# pstage.net
KiCad netlist of a schematic drawn in EAGLE
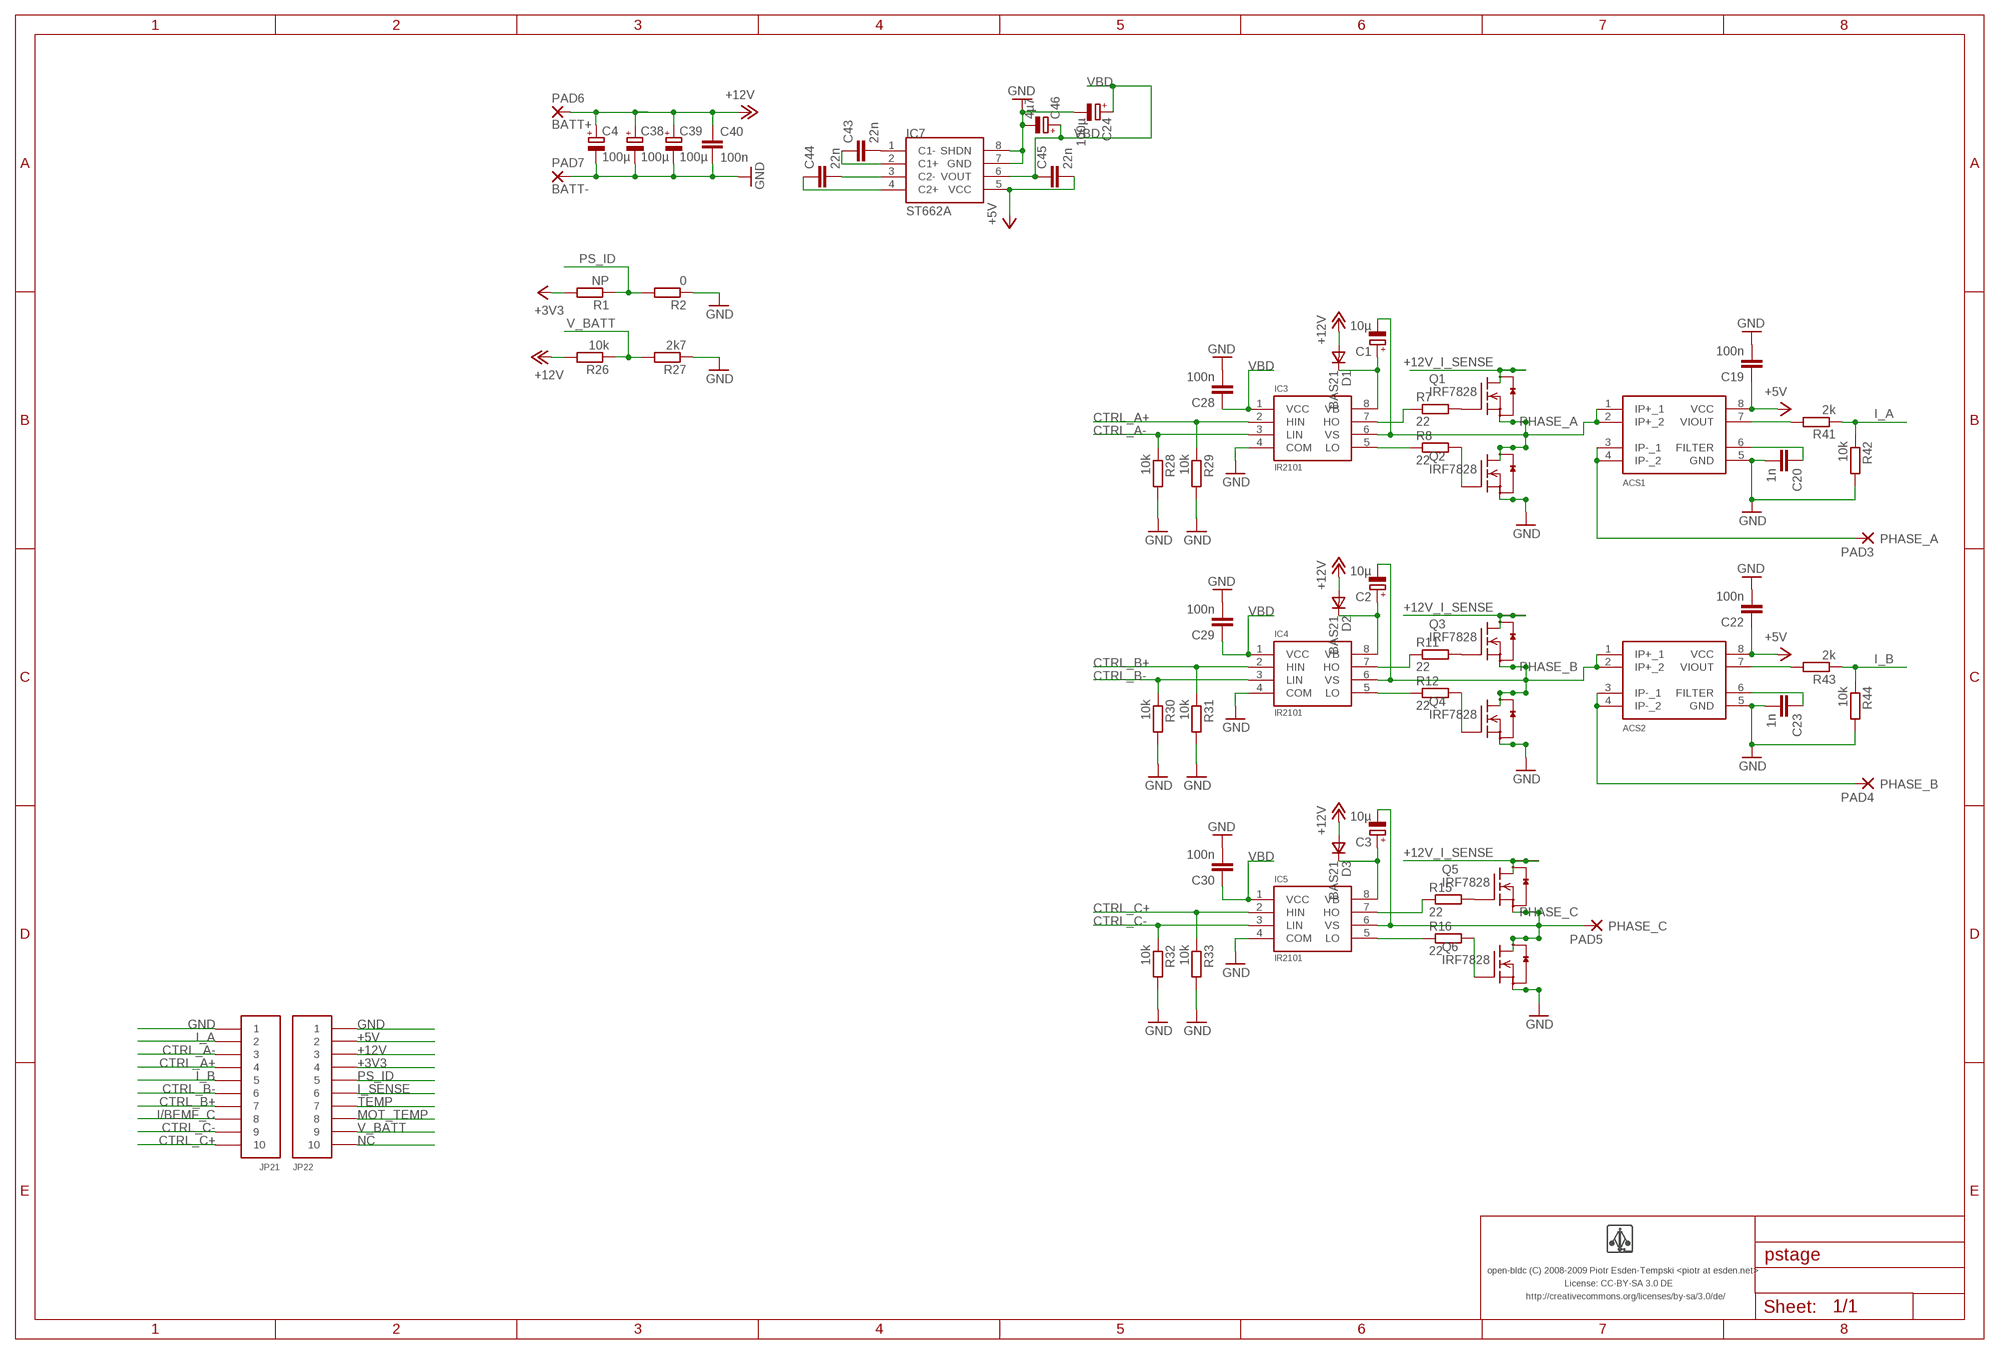
[diagram p0: schematic, sheet 1]

(export (version "E")
  (design (tool "Eeschema 10.0.6"))
  (components
    (comp (ref "ACS1")
      (value "ACS712")
      (footprint "eagle-import:SO8")
      (libsource (lib "eagle-import") (part "ACS712"))
    )
    (comp (ref "ACS2")
      (value "ACS712")
      (footprint "eagle-import:SO8")
      (libsource (lib "eagle-import") (part "ACS712"))
    )
    (comp (ref "C1")
      (value "10µ")
      (footprint "eagle-import:A_3216-18R")
      (libsource (lib "eagle-import") (part "CPOL-EUA/3216-18R"))
    )
    (comp (ref "C2")
      (value "10µ")
      (footprint "eagle-import:A_3216-18R")
      (libsource (lib "eagle-import") (part "CPOL-EUA/3216-18R"))
    )
    (comp (ref "C3")
      (value "10µ")
      (footprint "eagle-import:A_3216-18R")
      (libsource (lib "eagle-import") (part "CPOL-EUA/3216-18R"))
    )
    (comp (ref "C4")
      (value "100µ")
      (footprint "eagle-import:D_7343-31R")
      (libsource (lib "eagle-import") (part "CPOL-EUD/7343-31R"))
    )
    (comp (ref "C19")
      (value "100n")
      (footprint "eagle-import:C0603")
      (libsource (lib "eagle-import") (part "C-EUC0603"))
    )
    (comp (ref "C20")
      (value "1n")
      (footprint "eagle-import:C0603")
      (libsource (lib "eagle-import") (part "C-EUC0603"))
    )
    (comp (ref "C22")
      (value "100n")
      (footprint "eagle-import:C0603")
      (libsource (lib "eagle-import") (part "C-EUC0603"))
    )
    (comp (ref "C23")
      (value "1n")
      (footprint "eagle-import:C0603")
      (libsource (lib "eagle-import") (part "C-EUC0603"))
    )
    (comp (ref "C24")
      (value "100µ")
      (footprint "eagle-import:D_7343-31R")
      (libsource (lib "eagle-import") (part "CPOL-EUD/7343-31R"))
    )
    (comp (ref "C28")
      (value "100n")
      (footprint "eagle-import:C0603")
      (libsource (lib "eagle-import") (part "C-EUC0603"))
    )
    (comp (ref "C29")
      (value "100n")
      (footprint "eagle-import:C0603")
      (libsource (lib "eagle-import") (part "C-EUC0603"))
    )
    (comp (ref "C30")
      (value "100n")
      (footprint "eagle-import:C0603")
      (libsource (lib "eagle-import") (part "C-EUC0603"))
    )
    (comp (ref "C38")
      (value "100µ")
      (footprint "eagle-import:D_7343-31R")
      (libsource (lib "eagle-import") (part "CPOL-EUD/7343-31R"))
    )
    (comp (ref "C39")
      (value "100µ")
      (footprint "eagle-import:D_7343-31R")
      (libsource (lib "eagle-import") (part "CPOL-EUD/7343-31R"))
    )
    (comp (ref "C40")
      (value "100n")
      (footprint "eagle-import:C0603")
      (libsource (lib "eagle-import") (part "C-EUC0603"))
    )
    (comp (ref "C43")
      (value "22n")
      (footprint "eagle-import:C0603")
      (libsource (lib "eagle-import") (part "C-EUC0603"))
    )
    (comp (ref "C44")
      (value "22n")
      (footprint "eagle-import:C0603")
      (libsource (lib "eagle-import") (part "C-EUC0603"))
    )
    (comp (ref "C45")
      (value "22n")
      (footprint "eagle-import:C0603")
      (libsource (lib "eagle-import") (part "C-EUC0603"))
    )
    (comp (ref "C46")
      (value "4µ7")
      (footprint "eagle-import:A_3216-18R")
      (libsource (lib "eagle-import") (part "CPOL-EUA/3216-18R"))
    )
    (comp (ref "D1")
      (value "BAS21")
      (footprint "eagle-import:SOT-23")
      (libsource (lib "eagle-import") (part "VAR2SOT23"))
    )
    (comp (ref "D2")
      (value "BAS21")
      (footprint "eagle-import:SOT-23")
      (libsource (lib "eagle-import") (part "VAR2SOT23"))
    )
    (comp (ref "D3")
      (value "BAS21")
      (footprint "eagle-import:SOT-23")
      (libsource (lib "eagle-import") (part "VAR2SOT23"))
    )
    (comp (ref "IC3")
      (value "IR2101")
      (footprint "eagle-import:SO-8")
      (libsource (lib "eagle-import") (part "IR2101"))
    )
    (comp (ref "IC4")
      (value "IR2101")
      (footprint "eagle-import:SO-8")
      (libsource (lib "eagle-import") (part "IR2101"))
    )
    (comp (ref "IC5")
      (value "IR2101")
      (footprint "eagle-import:SO-8")
      (libsource (lib "eagle-import") (part "IR2101"))
    )
    (comp (ref "IC7")
      (value "ST662A")
      (footprint "eagle-import:SO8")
      (libsource (lib "eagle-import") (part "ST662A"))
    )
    (comp (ref "JP21")
      (value "PIN_HDR_1.27MM_10")
      (footprint "eagle-import:PIN_HDR_1.27MM_10")
      (libsource (lib "eagle-import") (part "PIN_HDR_1.27MM_10_TH"))
    )
    (comp (ref "JP22")
      (value "PIN_HDR_1.27MM_10")
      (footprint "eagle-import:PIN_HDR_1.27MM_10")
      (libsource (lib "eagle-import") (part "PIN_HDR_1.27MM_10_TH"))
    )
    (comp (ref "PAD3")
      (value "PHASE_A")
      (footprint "eagle-import:SMD2,54-5,08")
      (libsource (lib "eagle-import") (part "SMD5"))
    )
    (comp (ref "PAD4")
      (value "PHASE_B")
      (footprint "eagle-import:SMD2,54-5,08")
      (libsource (lib "eagle-import") (part "SMD5"))
    )
    (comp (ref "PAD5")
      (value "PHASE_C")
      (footprint "eagle-import:SMD2,54-5,08")
      (libsource (lib "eagle-import") (part "SMD5"))
    )
    (comp (ref "PAD6")
      (value "BATT+")
      (footprint "eagle-import:SMD2,54-5,08")
      (libsource (lib "eagle-import") (part "SMD5"))
    )
    (comp (ref "PAD7")
      (value "BATT-")
      (footprint "eagle-import:SMD2,54-5,08")
      (libsource (lib "eagle-import") (part "SMD5"))
    )
    (comp (ref "Q1")
      (value "IRF7828")
      (footprint "eagle-import:SO8")
      (libsource (lib "eagle-import") (part "IRF7828"))
    )
    (comp (ref "Q2")
      (value "IRF7828")
      (footprint "eagle-import:SO8")
      (libsource (lib "eagle-import") (part "IRF7828"))
    )
    (comp (ref "Q3")
      (value "IRF7828")
      (footprint "eagle-import:SO8")
      (libsource (lib "eagle-import") (part "IRF7828"))
    )
    (comp (ref "Q4")
      (value "IRF7828")
      (footprint "eagle-import:SO8")
      (libsource (lib "eagle-import") (part "IRF7828"))
    )
    (comp (ref "Q5")
      (value "IRF7828")
      (footprint "eagle-import:SO8")
      (libsource (lib "eagle-import") (part "IRF7828"))
    )
    (comp (ref "Q6")
      (value "IRF7828")
      (footprint "eagle-import:SO8")
      (libsource (lib "eagle-import") (part "IRF7828"))
    )
    (comp (ref "R1")
      (value "NP")
      (footprint "eagle-import:R0603")
      (libsource (lib "eagle-import") (part "R-EU_R0603"))
    )
    (comp (ref "R2")
      (value "0")
      (footprint "eagle-import:R0603")
      (libsource (lib "eagle-import") (part "R-EU_R0603"))
    )
    (comp (ref "R7")
      (value "22")
      (footprint "eagle-import:R0603")
      (libsource (lib "eagle-import") (part "R-EU_R0603"))
    )
    (comp (ref "R8")
      (value "22")
      (footprint "eagle-import:R0603")
      (libsource (lib "eagle-import") (part "R-EU_R0603"))
    )
    (comp (ref "R11")
      (value "22")
      (footprint "eagle-import:R0603")
      (libsource (lib "eagle-import") (part "R-EU_R0603"))
    )
    (comp (ref "R12")
      (value "22")
      (footprint "eagle-import:R0603")
      (libsource (lib "eagle-import") (part "R-EU_R0603"))
    )
    (comp (ref "R15")
      (value "22")
      (footprint "eagle-import:R0603")
      (libsource (lib "eagle-import") (part "R-EU_R0603"))
    )
    (comp (ref "R16")
      (value "22")
      (footprint "eagle-import:R0603")
      (libsource (lib "eagle-import") (part "R-EU_R0603"))
    )
    (comp (ref "R26")
      (value "10k")
      (footprint "eagle-import:R0603")
      (libsource (lib "eagle-import") (part "R-EU_R0603"))
    )
    (comp (ref "R27")
      (value "2k7")
      (footprint "eagle-import:R0603")
      (libsource (lib "eagle-import") (part "R-EU_R0603"))
    )
    (comp (ref "R28")
      (value "10k")
      (footprint "eagle-import:R0603")
      (libsource (lib "eagle-import") (part "R-EU_R0603"))
    )
    (comp (ref "R29")
      (value "10k")
      (footprint "eagle-import:R0603")
      (libsource (lib "eagle-import") (part "R-EU_R0603"))
    )
    (comp (ref "R30")
      (value "10k")
      (footprint "eagle-import:R0603")
      (libsource (lib "eagle-import") (part "R-EU_R0603"))
    )
    (comp (ref "R31")
      (value "10k")
      (footprint "eagle-import:R0603")
      (libsource (lib "eagle-import") (part "R-EU_R0603"))
    )
    (comp (ref "R32")
      (value "10k")
      (footprint "eagle-import:R0603")
      (libsource (lib "eagle-import") (part "R-EU_R0603"))
    )
    (comp (ref "R33")
      (value "10k")
      (footprint "eagle-import:R0603")
      (libsource (lib "eagle-import") (part "R-EU_R0603"))
    )
    (comp (ref "R41")
      (value "2k")
      (footprint "eagle-import:R0603")
      (libsource (lib "eagle-import") (part "R-EU_R0603"))
    )
    (comp (ref "R42")
      (value "10k")
      (footprint "eagle-import:R0603")
      (libsource (lib "eagle-import") (part "R-EU_R0603"))
    )
    (comp (ref "R43")
      (value "2k")
      (footprint "eagle-import:R0603")
      (libsource (lib "eagle-import") (part "R-EU_R0603"))
    )
    (comp (ref "R44")
      (value "10k")
      (footprint "eagle-import:R0603")
      (libsource (lib "eagle-import") (part "R-EU_R0603"))
    )
    (comp (ref "U$1")
      (value "LOGO")
      (footprint "eagle-import:LOGO")
      (libsource (lib "eagle-import") (part "LOGO"))
    )
  )
  (nets
    (net (code "1") (name "+3V3") (class "Default")
      (node (ref "JP22") (pin "P$4") (pinfunction "4_P$4") (pintype "bidirectional"))
      (node (ref "R1") (pin "2") (pinfunction "2_2") (pintype "passive"))
    )
    (net (code "2") (name "+5V") (class "Default")
      (node (ref "ACS1") (pin "8") (pinfunction "VCC_8") (pintype "bidirectional"))
      (node (ref "ACS2") (pin "8") (pinfunction "VCC_8") (pintype "bidirectional"))
      (node (ref "C19") (pin "1") (pinfunction "1_1") (pintype "passive"))
      (node (ref "C22") (pin "1") (pinfunction "1_1") (pintype "passive"))
      (node (ref "C45") (pin "2") (pinfunction "2_2") (pintype "passive"))
      (node (ref "IC7") (pin "5") (pinfunction "VCC_5") (pintype "bidirectional"))
      (node (ref "JP22") (pin "P$2") (pinfunction "2_P$2") (pintype "bidirectional"))
    )
    (net (code "3") (name "+12V") (class "Default")
      (node (ref "C38") (pin "+") (pinfunction "+_+") (pintype "passive"))
      (node (ref "C39") (pin "+") (pinfunction "+_+") (pintype "passive"))
      (node (ref "C4") (pin "+") (pinfunction "+_+") (pintype "passive"))
      (node (ref "C40") (pin "1") (pinfunction "1_1") (pintype "passive"))
      (node (ref "D1") (pin "3") (pinfunction "A_3") (pintype "passive"))
      (node (ref "D2") (pin "3") (pinfunction "A_3") (pintype "passive"))
      (node (ref "D3") (pin "3") (pinfunction "A_3") (pintype "passive"))
      (node (ref "JP22") (pin "P$3") (pinfunction "3_P$3") (pintype "bidirectional"))
      (node (ref "PAD6") (pin "1") (pinfunction "P_1") (pintype "passive"))
      (node (ref "R26") (pin "2") (pinfunction "2_2") (pintype "passive"))
    )
    (net (code "4") (name "/+12V_I_SENSE") (class "Default")
      (node (ref "Q1") (pin "5") (pinfunction "D1_5") (pintype "passive"))
      (node (ref "Q1") (pin "6") (pinfunction "D2_6") (pintype "passive"))
      (node (ref "Q1") (pin "7") (pinfunction "D3_7") (pintype "passive"))
      (node (ref "Q1") (pin "8") (pinfunction "D4_8") (pintype "passive"))
      (node (ref "Q3") (pin "5") (pinfunction "D1_5") (pintype "passive"))
      (node (ref "Q3") (pin "6") (pinfunction "D2_6") (pintype "passive"))
      (node (ref "Q3") (pin "7") (pinfunction "D3_7") (pintype "passive"))
      (node (ref "Q3") (pin "8") (pinfunction "D4_8") (pintype "passive"))
      (node (ref "Q5") (pin "5") (pinfunction "D1_5") (pintype "passive"))
      (node (ref "Q5") (pin "6") (pinfunction "D2_6") (pintype "passive"))
      (node (ref "Q5") (pin "7") (pinfunction "D3_7") (pintype "passive"))
      (node (ref "Q5") (pin "8") (pinfunction "D4_8") (pintype "passive"))
    )
    (net (code "5") (name "/CTRL_A+") (class "Default")
      (node (ref "IC3") (pin "2") (pinfunction "HIN_2") (pintype "bidirectional"))
      (node (ref "JP21") (pin "P$4") (pinfunction "4_P$4") (pintype "bidirectional"))
      (node (ref "R29") (pin "1") (pinfunction "1_1") (pintype "passive"))
    )
    (net (code "6") (name "/CTRL_A-") (class "Default")
      (node (ref "IC3") (pin "3") (pinfunction "LIN_3") (pintype "bidirectional"))
      (node (ref "JP21") (pin "P$3") (pinfunction "3_P$3") (pintype "bidirectional"))
      (node (ref "R28") (pin "1") (pinfunction "1_1") (pintype "passive"))
    )
    (net (code "7") (name "/CTRL_B+") (class "Default")
      (node (ref "IC4") (pin "2") (pinfunction "HIN_2") (pintype "bidirectional"))
      (node (ref "JP21") (pin "P$7") (pinfunction "7_P$7") (pintype "bidirectional"))
      (node (ref "R31") (pin "1") (pinfunction "1_1") (pintype "passive"))
    )
    (net (code "8") (name "/CTRL_B-") (class "Default")
      (node (ref "IC4") (pin "3") (pinfunction "LIN_3") (pintype "bidirectional"))
      (node (ref "JP21") (pin "P$6") (pinfunction "6_P$6") (pintype "bidirectional"))
      (node (ref "R30") (pin "1") (pinfunction "1_1") (pintype "passive"))
    )
    (net (code "9") (name "/CTRL_C+") (class "Default")
      (node (ref "IC5") (pin "2") (pinfunction "HIN_2") (pintype "bidirectional"))
      (node (ref "JP21") (pin "P$10") (pinfunction "10_P$10") (pintype "bidirectional"))
      (node (ref "R33") (pin "1") (pinfunction "1_1") (pintype "passive"))
    )
    (net (code "10") (name "/CTRL_C-") (class "Default")
      (node (ref "IC5") (pin "3") (pinfunction "LIN_3") (pintype "bidirectional"))
      (node (ref "JP21") (pin "P$9") (pinfunction "9_P$9") (pintype "bidirectional"))
      (node (ref "R32") (pin "1") (pinfunction "1_1") (pintype "passive"))
    )
    (net (code "11") (name "/I_A") (class "Default")
      (node (ref "JP21") (pin "P$2") (pinfunction "2_P$2") (pintype "bidirectional"))
      (node (ref "R41") (pin "1") (pinfunction "1_1") (pintype "passive"))
      (node (ref "R42") (pin "1") (pinfunction "1_1") (pintype "passive"))
    )
    (net (code "12") (name "/I_B") (class "Default")
      (node (ref "JP21") (pin "P$5") (pinfunction "5_P$5") (pintype "bidirectional"))
      (node (ref "R43") (pin "1") (pinfunction "1_1") (pintype "passive"))
      (node (ref "R44") (pin "1") (pinfunction "1_1") (pintype "passive"))
    )
    (net (code "13") (name "/I_SENSE") (class "Default")
      (node (ref "JP22") (pin "P$6") (pinfunction "6_P$6") (pintype "bidirectional"))
    )
    (net (code "14") (name "/I{slash}BEMF_C") (class "Default")
      (node (ref "JP21") (pin "P$8") (pinfunction "8_P$8") (pintype "bidirectional"))
    )
    (net (code "15") (name "/MOT_TEMP") (class "Default")
      (node (ref "JP22") (pin "P$8") (pinfunction "8_P$8") (pintype "bidirectional"))
    )
    (net (code "16") (name "/NC") (class "Default")
      (node (ref "JP22") (pin "P$10") (pinfunction "10_P$10") (pintype "bidirectional"))
    )
    (net (code "17") (name "/PHASE_A") (class "Default")
      (node (ref "ACS1") (pin "1") (pinfunction "IP+_1_1") (pintype "bidirectional"))
      (node (ref "ACS1") (pin "2") (pinfunction "IP+_2_2") (pintype "bidirectional"))
      (node (ref "C1") (pin "-") (pinfunction "-_-") (pintype "passive"))
      (node (ref "IC3") (pin "6") (pinfunction "VS_6") (pintype "bidirectional"))
      (node (ref "Q1") (pin "1") (pinfunction "S3_1") (pintype "passive"))
      (node (ref "Q1") (pin "2") (pinfunction "S2_2") (pintype "passive"))
      (node (ref "Q1") (pin "3") (pinfunction "S1_3") (pintype "passive"))
      (node (ref "Q2") (pin "5") (pinfunction "D1_5") (pintype "passive"))
      (node (ref "Q2") (pin "6") (pinfunction "D2_6") (pintype "passive"))
      (node (ref "Q2") (pin "7") (pinfunction "D3_7") (pintype "passive"))
      (node (ref "Q2") (pin "8") (pinfunction "D4_8") (pintype "passive"))
    )
    (net (code "18") (name "/PHASE_B") (class "Default")
      (node (ref "ACS2") (pin "1") (pinfunction "IP+_1_1") (pintype "bidirectional"))
      (node (ref "ACS2") (pin "2") (pinfunction "IP+_2_2") (pintype "bidirectional"))
      (node (ref "C2") (pin "-") (pinfunction "-_-") (pintype "passive"))
      (node (ref "IC4") (pin "6") (pinfunction "VS_6") (pintype "bidirectional"))
      (node (ref "Q3") (pin "1") (pinfunction "S3_1") (pintype "passive"))
      (node (ref "Q3") (pin "2") (pinfunction "S2_2") (pintype "passive"))
      (node (ref "Q3") (pin "3") (pinfunction "S1_3") (pintype "passive"))
      (node (ref "Q4") (pin "5") (pinfunction "D1_5") (pintype "passive"))
      (node (ref "Q4") (pin "6") (pinfunction "D2_6") (pintype "passive"))
      (node (ref "Q4") (pin "7") (pinfunction "D3_7") (pintype "passive"))
      (node (ref "Q4") (pin "8") (pinfunction "D4_8") (pintype "passive"))
    )
    (net (code "19") (name "/PHASE_C") (class "Default")
      (node (ref "C3") (pin "-") (pinfunction "-_-") (pintype "passive"))
      (node (ref "IC5") (pin "6") (pinfunction "VS_6") (pintype "bidirectional"))
      (node (ref "PAD5") (pin "1") (pinfunction "P_1") (pintype "passive"))
      (node (ref "Q5") (pin "1") (pinfunction "S3_1") (pintype "passive"))
      (node (ref "Q5") (pin "2") (pinfunction "S2_2") (pintype "passive"))
      (node (ref "Q5") (pin "3") (pinfunction "S1_3") (pintype "passive"))
      (node (ref "Q6") (pin "5") (pinfunction "D1_5") (pintype "passive"))
      (node (ref "Q6") (pin "6") (pinfunction "D2_6") (pintype "passive"))
      (node (ref "Q6") (pin "7") (pinfunction "D3_7") (pintype "passive"))
      (node (ref "Q6") (pin "8") (pinfunction "D4_8") (pintype "passive"))
    )
    (net (code "20") (name "/PS_ID") (class "Default")
      (node (ref "JP22") (pin "P$5") (pinfunction "5_P$5") (pintype "bidirectional"))
      (node (ref "R1") (pin "1") (pinfunction "1_1") (pintype "passive"))
      (node (ref "R2") (pin "2") (pinfunction "2_2") (pintype "passive"))
    )
    (net (code "21") (name "/TEMP") (class "Default")
      (node (ref "JP22") (pin "P$7") (pinfunction "7_P$7") (pintype "bidirectional"))
    )
    (net (code "22") (name "/VBD") (class "Default")
      (node (ref "C24") (pin "+") (pinfunction "+_+") (pintype "passive"))
      (node (ref "C28") (pin "1") (pinfunction "1_1") (pintype "passive"))
      (node (ref "C29") (pin "1") (pinfunction "1_1") (pintype "passive"))
      (node (ref "C30") (pin "1") (pinfunction "1_1") (pintype "passive"))
      (node (ref "C45") (pin "1") (pinfunction "1_1") (pintype "passive"))
      (node (ref "C46") (pin "+") (pinfunction "+_+") (pintype "passive"))
      (node (ref "IC3") (pin "1") (pinfunction "VCC_1") (pintype "bidirectional"))
      (node (ref "IC4") (pin "1") (pinfunction "VCC_1") (pintype "bidirectional"))
      (node (ref "IC5") (pin "1") (pinfunction "VCC_1") (pintype "bidirectional"))
      (node (ref "IC7") (pin "6") (pinfunction "VOUT_6") (pintype "bidirectional"))
    )
    (net (code "23") (name "/V_BATT") (class "Default")
      (node (ref "JP22") (pin "P$9") (pinfunction "9_P$9") (pintype "bidirectional"))
      (node (ref "R26") (pin "1") (pinfunction "1_1") (pintype "passive"))
      (node (ref "R27") (pin "2") (pinfunction "2_2") (pintype "passive"))
    )
    (net (code "24") (name "GND") (class "Default")
      (node (ref "ACS1") (pin "5") (pinfunction "GND_5") (pintype "bidirectional"))
      (node (ref "ACS2") (pin "5") (pinfunction "GND_5") (pintype "bidirectional"))
      (node (ref "C19") (pin "2") (pinfunction "2_2") (pintype "passive"))
      (node (ref "C20") (pin "2") (pinfunction "2_2") (pintype "passive"))
      (node (ref "C22") (pin "2") (pinfunction "2_2") (pintype "passive"))
      (node (ref "C23") (pin "2") (pinfunction "2_2") (pintype "passive"))
      (node (ref "C24") (pin "-") (pinfunction "-_-") (pintype "passive"))
      (node (ref "C28") (pin "2") (pinfunction "2_2") (pintype "passive"))
      (node (ref "C29") (pin "2") (pinfunction "2_2") (pintype "passive"))
      (node (ref "C30") (pin "2") (pinfunction "2_2") (pintype "passive"))
      (node (ref "C38") (pin "-") (pinfunction "-_-") (pintype "passive"))
      (node (ref "C39") (pin "-") (pinfunction "-_-") (pintype "passive"))
      (node (ref "C4") (pin "-") (pinfunction "-_-") (pintype "passive"))
      (node (ref "C40") (pin "2") (pinfunction "2_2") (pintype "passive"))
      (node (ref "C46") (pin "-") (pinfunction "-_-") (pintype "passive"))
      (node (ref "IC3") (pin "4") (pinfunction "COM_4") (pintype "bidirectional"))
      (node (ref "IC4") (pin "4") (pinfunction "COM_4") (pintype "bidirectional"))
      (node (ref "IC5") (pin "4") (pinfunction "COM_4") (pintype "bidirectional"))
      (node (ref "IC7") (pin "7") (pinfunction "GND_7") (pintype "bidirectional"))
      (node (ref "IC7") (pin "8") (pinfunction "SHDN_8") (pintype "bidirectional"))
      (node (ref "JP21") (pin "P$1") (pinfunction "1_P$1") (pintype "bidirectional"))
      (node (ref "JP22") (pin "P$1") (pinfunction "1_P$1") (pintype "bidirectional"))
      (node (ref "PAD7") (pin "1") (pinfunction "P_1") (pintype "passive"))
      (node (ref "Q2") (pin "1") (pinfunction "S3_1") (pintype "passive"))
      (node (ref "Q2") (pin "2") (pinfunction "S2_2") (pintype "passive"))
      (node (ref "Q2") (pin "3") (pinfunction "S1_3") (pintype "passive"))
      (node (ref "Q4") (pin "1") (pinfunction "S3_1") (pintype "passive"))
      (node (ref "Q4") (pin "2") (pinfunction "S2_2") (pintype "passive"))
      (node (ref "Q4") (pin "3") (pinfunction "S1_3") (pintype "passive"))
      (node (ref "Q6") (pin "1") (pinfunction "S3_1") (pintype "passive"))
      (node (ref "Q6") (pin "2") (pinfunction "S2_2") (pintype "passive"))
      (node (ref "Q6") (pin "3") (pinfunction "S1_3") (pintype "passive"))
      (node (ref "R2") (pin "1") (pinfunction "1_1") (pintype "passive"))
      (node (ref "R27") (pin "1") (pinfunction "1_1") (pintype "passive"))
      (node (ref "R28") (pin "2") (pinfunction "2_2") (pintype "passive"))
      (node (ref "R29") (pin "2") (pinfunction "2_2") (pintype "passive"))
      (node (ref "R30") (pin "2") (pinfunction "2_2") (pintype "passive"))
      (node (ref "R31") (pin "2") (pinfunction "2_2") (pintype "passive"))
      (node (ref "R32") (pin "2") (pinfunction "2_2") (pintype "passive"))
      (node (ref "R33") (pin "2") (pinfunction "2_2") (pintype "passive"))
      (node (ref "R42") (pin "2") (pinfunction "2_2") (pintype "passive"))
      (node (ref "R44") (pin "2") (pinfunction "2_2") (pintype "passive"))
    )
    (net (code "25") (name "Net-(ACS1-FILTER)") (class "Default")
      (node (ref "ACS1") (pin "6") (pinfunction "FILTER_6") (pintype "bidirectional"))
      (node (ref "C20") (pin "1") (pinfunction "1_1") (pintype "passive"))
    )
    (net (code "26") (name "Net-(ACS1-IP-_1)") (class "Default")
      (node (ref "ACS1") (pin "3") (pinfunction "IP-_1_3") (pintype "bidirectional"))
      (node (ref "ACS1") (pin "4") (pinfunction "IP-_2_4") (pintype "bidirectional"))
      (node (ref "PAD3") (pin "1") (pinfunction "P_1") (pintype "passive"))
    )
    (net (code "27") (name "Net-(ACS1-VIOUT)") (class "Default")
      (node (ref "ACS1") (pin "7") (pinfunction "VIOUT_7") (pintype "bidirectional"))
      (node (ref "R41") (pin "2") (pinfunction "2_2") (pintype "passive"))
    )
    (net (code "28") (name "Net-(ACS2-FILTER)") (class "Default")
      (node (ref "ACS2") (pin "6") (pinfunction "FILTER_6") (pintype "bidirectional"))
      (node (ref "C23") (pin "1") (pinfunction "1_1") (pintype "passive"))
    )
    (net (code "29") (name "Net-(ACS2-IP-_1)") (class "Default")
      (node (ref "ACS2") (pin "3") (pinfunction "IP-_1_3") (pintype "bidirectional"))
      (node (ref "ACS2") (pin "4") (pinfunction "IP-_2_4") (pintype "bidirectional"))
      (node (ref "PAD4") (pin "1") (pinfunction "P_1") (pintype "passive"))
    )
    (net (code "30") (name "Net-(ACS2-VIOUT)") (class "Default")
      (node (ref "ACS2") (pin "7") (pinfunction "VIOUT_7") (pintype "bidirectional"))
      (node (ref "R43") (pin "2") (pinfunction "2_2") (pintype "passive"))
    )
    (net (code "31") (name "Net-(D1-C)") (class "Default")
      (node (ref "C1") (pin "+") (pinfunction "+_+") (pintype "passive"))
      (node (ref "D1") (pin "1") (pinfunction "C_1") (pintype "passive"))
      (node (ref "IC3") (pin "8") (pinfunction "VB_8") (pintype "bidirectional"))
    )
    (net (code "32") (name "Net-(D2-C)") (class "Default")
      (node (ref "C2") (pin "+") (pinfunction "+_+") (pintype "passive"))
      (node (ref "D2") (pin "1") (pinfunction "C_1") (pintype "passive"))
      (node (ref "IC4") (pin "8") (pinfunction "VB_8") (pintype "bidirectional"))
    )
    (net (code "33") (name "Net-(D3-C)") (class "Default")
      (node (ref "C3") (pin "+") (pinfunction "+_+") (pintype "passive"))
      (node (ref "D3") (pin "1") (pinfunction "C_1") (pintype "passive"))
      (node (ref "IC5") (pin "8") (pinfunction "VB_8") (pintype "bidirectional"))
    )
    (net (code "34") (name "Net-(IC3-HO)") (class "Default")
      (node (ref "IC3") (pin "7") (pinfunction "HO_7") (pintype "bidirectional"))
      (node (ref "R7") (pin "1") (pinfunction "1_1") (pintype "passive"))
    )
    (net (code "35") (name "Net-(IC3-LO)") (class "Default")
      (node (ref "IC3") (pin "5") (pinfunction "LO_5") (pintype "bidirectional"))
      (node (ref "R8") (pin "1") (pinfunction "1_1") (pintype "passive"))
    )
    (net (code "36") (name "Net-(IC4-HO)") (class "Default")
      (node (ref "IC4") (pin "7") (pinfunction "HO_7") (pintype "bidirectional"))
      (node (ref "R11") (pin "1") (pinfunction "1_1") (pintype "passive"))
    )
    (net (code "37") (name "Net-(IC4-LO)") (class "Default")
      (node (ref "IC4") (pin "5") (pinfunction "LO_5") (pintype "bidirectional"))
      (node (ref "R12") (pin "1") (pinfunction "1_1") (pintype "passive"))
    )
    (net (code "38") (name "Net-(IC5-HO)") (class "Default")
      (node (ref "IC5") (pin "7") (pinfunction "HO_7") (pintype "bidirectional"))
      (node (ref "R15") (pin "1") (pinfunction "1_1") (pintype "passive"))
    )
    (net (code "39") (name "Net-(IC5-LO)") (class "Default")
      (node (ref "IC5") (pin "5") (pinfunction "LO_5") (pintype "bidirectional"))
      (node (ref "R16") (pin "1") (pinfunction "1_1") (pintype "passive"))
    )
    (net (code "40") (name "Net-(IC7-C1+)") (class "Default")
      (node (ref "C43") (pin "1") (pinfunction "1_1") (pintype "passive"))
      (node (ref "IC7") (pin "2") (pinfunction "C1+_2") (pintype "bidirectional"))
    )
    (net (code "41") (name "Net-(IC7-C1-)") (class "Default")
      (node (ref "C43") (pin "2") (pinfunction "2_2") (pintype "passive"))
      (node (ref "IC7") (pin "1") (pinfunction "C1-_1") (pintype "bidirectional"))
    )
    (net (code "42") (name "Net-(IC7-C2+)") (class "Default")
      (node (ref "C44") (pin "1") (pinfunction "1_1") (pintype "passive"))
      (node (ref "IC7") (pin "4") (pinfunction "C2+_4") (pintype "bidirectional"))
    )
    (net (code "43") (name "Net-(IC7-C2-)") (class "Default")
      (node (ref "C44") (pin "2") (pinfunction "2_2") (pintype "passive"))
      (node (ref "IC7") (pin "3") (pinfunction "C2-_3") (pintype "bidirectional"))
    )
    (net (code "44") (name "Net-(Q1-G)") (class "Default")
      (node (ref "Q1") (pin "4") (pinfunction "G_4") (pintype "passive"))
      (node (ref "R7") (pin "2") (pinfunction "2_2") (pintype "passive"))
    )
    (net (code "45") (name "Net-(Q2-G)") (class "Default")
      (node (ref "Q2") (pin "4") (pinfunction "G_4") (pintype "passive"))
      (node (ref "R8") (pin "2") (pinfunction "2_2") (pintype "passive"))
    )
    (net (code "46") (name "Net-(Q3-G)") (class "Default")
      (node (ref "Q3") (pin "4") (pinfunction "G_4") (pintype "passive"))
      (node (ref "R11") (pin "2") (pinfunction "2_2") (pintype "passive"))
    )
    (net (code "47") (name "Net-(Q4-G)") (class "Default")
      (node (ref "Q4") (pin "4") (pinfunction "G_4") (pintype "passive"))
      (node (ref "R12") (pin "2") (pinfunction "2_2") (pintype "passive"))
    )
    (net (code "48") (name "Net-(Q5-G)") (class "Default")
      (node (ref "Q5") (pin "4") (pinfunction "G_4") (pintype "passive"))
      (node (ref "R15") (pin "2") (pinfunction "2_2") (pintype "passive"))
    )
    (net (code "49") (name "Net-(Q6-G)") (class "Default")
      (node (ref "Q6") (pin "4") (pinfunction "G_4") (pintype "passive"))
      (node (ref "R16") (pin "2") (pinfunction "2_2") (pintype "passive"))
    )
  )
)
